# MCU.net
KiCad netlist of a schematic drawn in Altium Designer
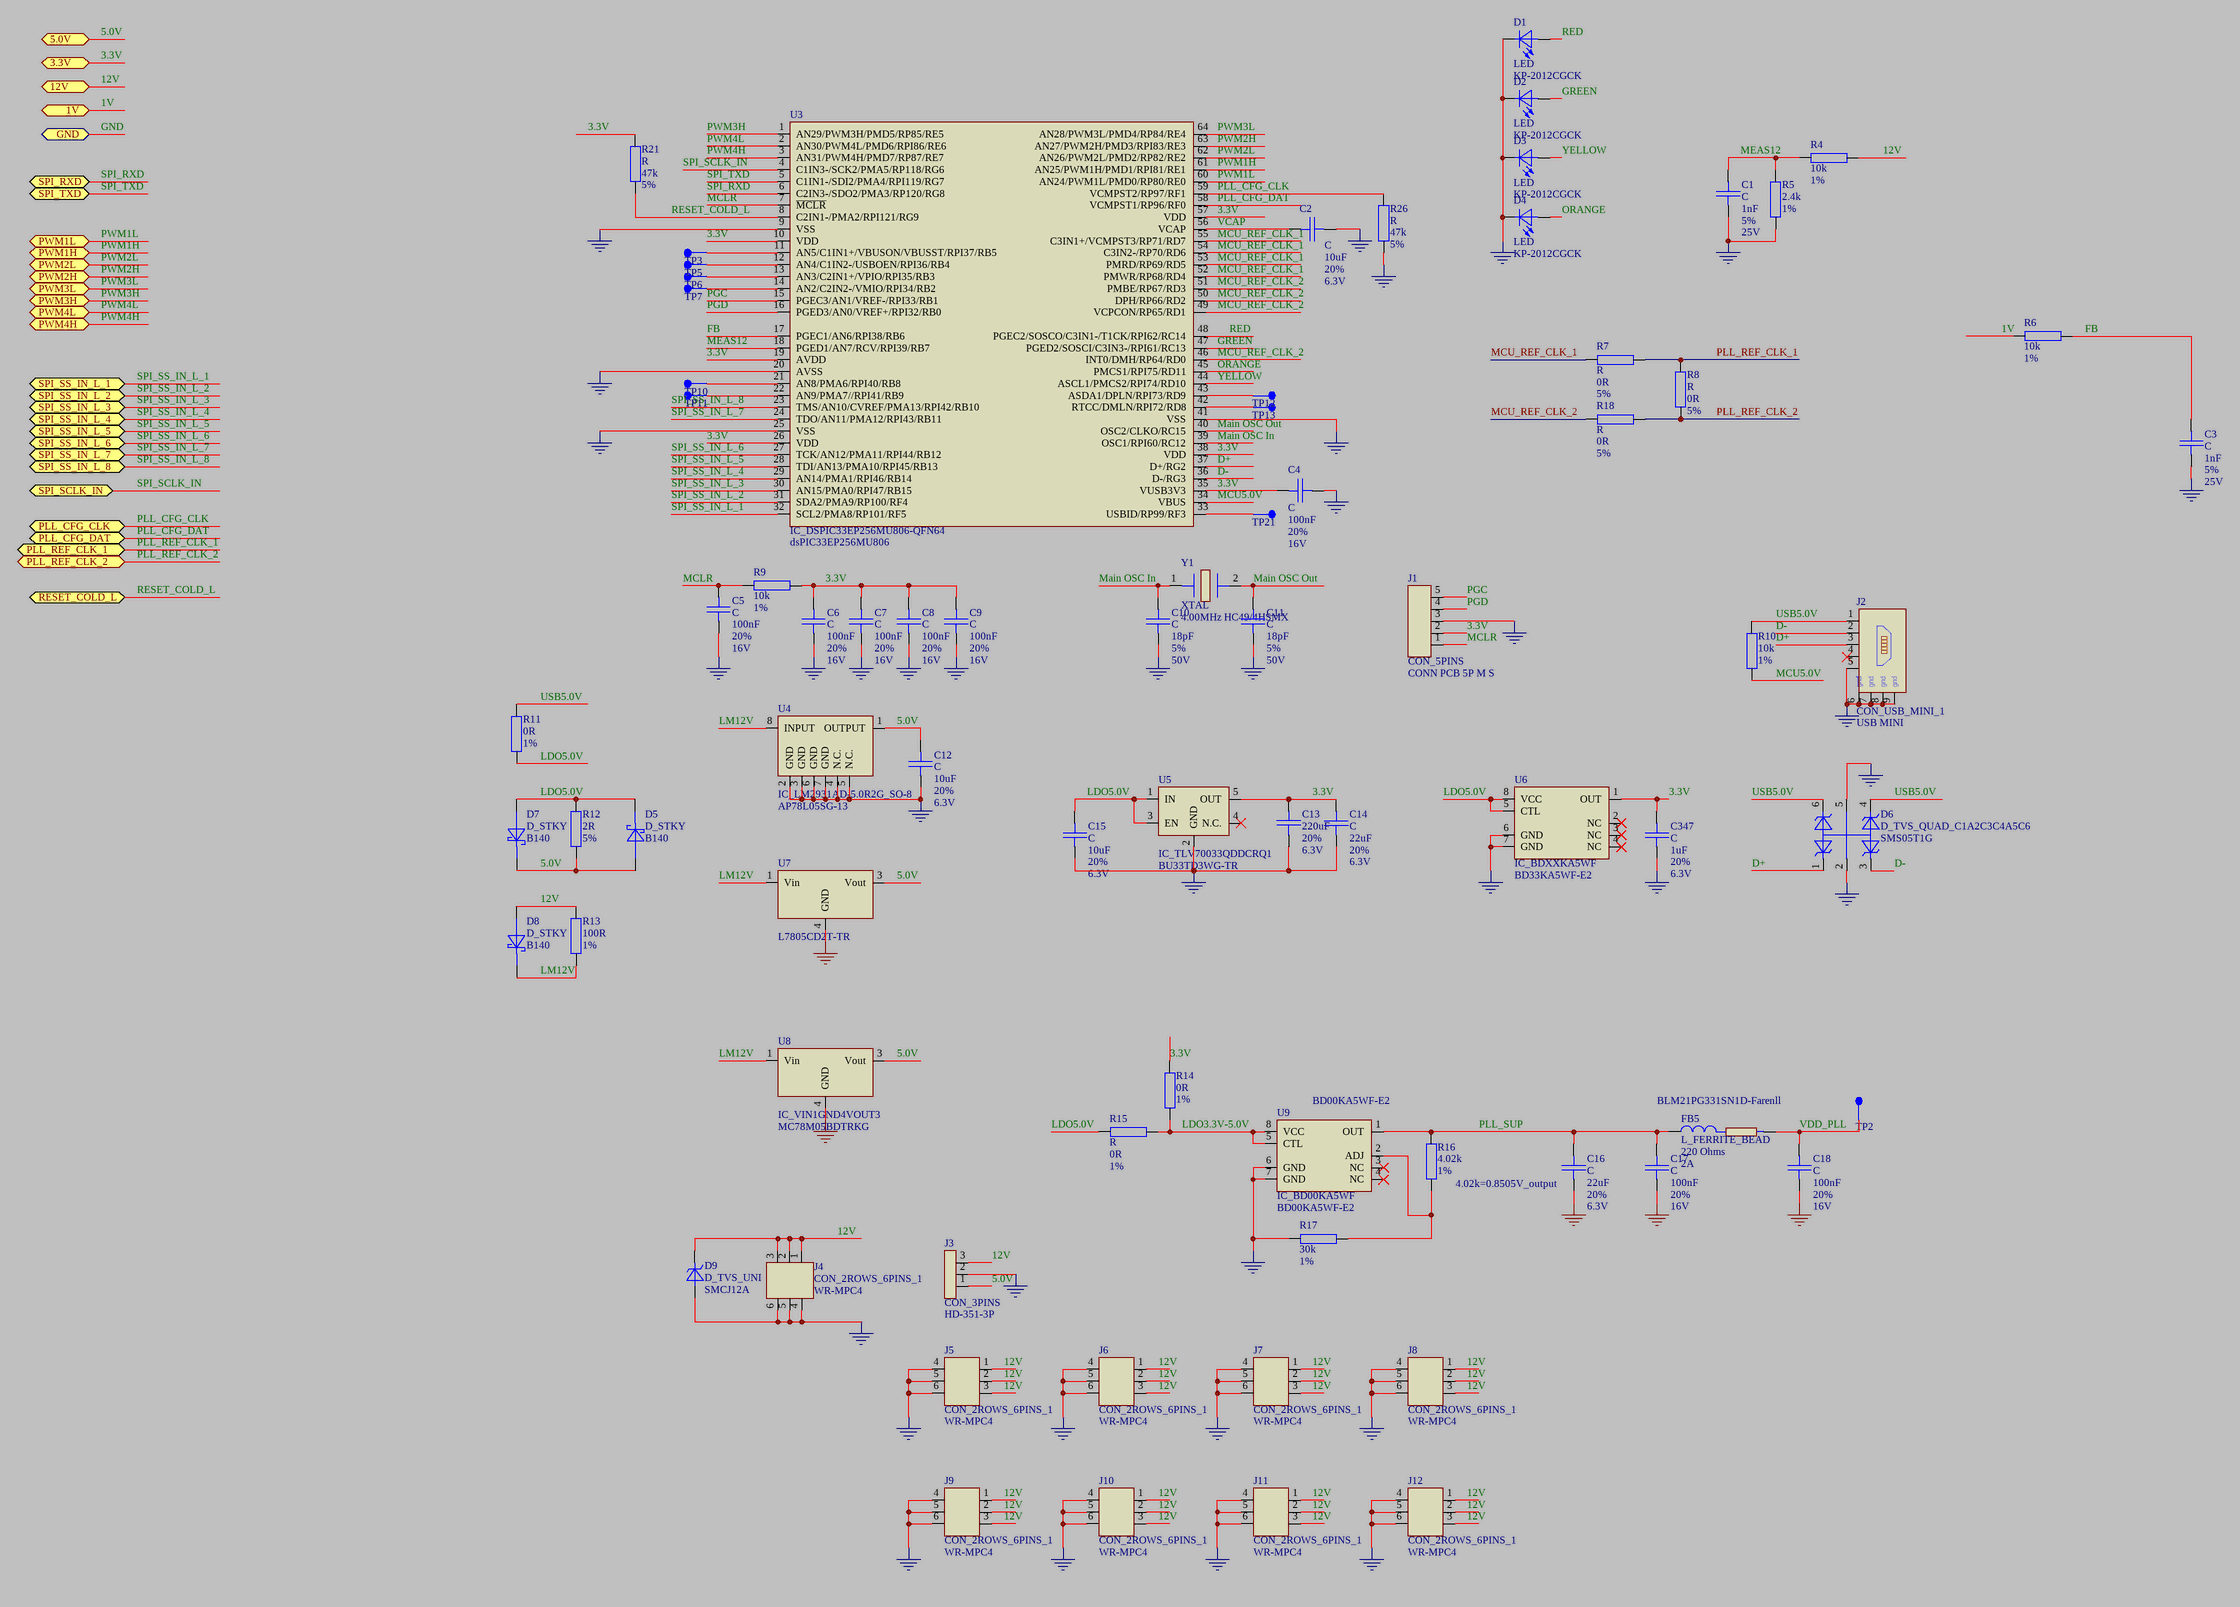
[diagram p0: MCU.SchDoc]

(export (version "E")
  (design (tool "Eeschema 10.0.6"))
  (components
    (comp (ref "C1")
      (value "C")
      (footprint "SMD_0603_CAPC1608X95N")
      (fields
        (field (name "DB_PART_NUMBER") "CAP000024113")
        (field (name "DB_VALUE") "1nF")
        (field (name "DB_TOLERANCE") "5%")
        (field (name "DB_VOLTAGE") "25V")
        (field (name "DB_MANUFACTURER_PART") "KEMET    C0603C102J3RAC")
      )
      (libsource (lib "Database_Libs1") (part "C"))
    )
    (comp (ref "C2")
      (value "C")
      (footprint "SMD_0603_CAPC1608X95N")
      (fields
        (field (name "DB_PART_NUMBER") "CAP000043646")
        (field (name "DB_VALUE") "10uF")
        (field (name "DB_TOLERANCE") "20%")
        (field (name "DB_VOLTAGE") "6.3V")
        (field (name "DB_MANUFACTURER_PART") "KEMET    C0603C106M9PAC")
      )
      (libsource (lib "Database_Libs1") (part "C"))
    )
    (comp (ref "C3")
      (value "C")
      (footprint "SMD_0603_CAPC1608X95N")
      (fields
        (field (name "DB_PART_NUMBER") "CAP000024113")
        (field (name "DB_VALUE") "1nF")
        (field (name "DB_TOLERANCE") "5%")
        (field (name "DB_VOLTAGE") "25V")
        (field (name "DB_MANUFACTURER_PART") "KEMET    C0603C102J3RAC")
      )
      (libsource (lib "Database_Libs1") (part "C"))
    )
    (comp (ref "C4")
      (value "C")
      (footprint "SMD_0402_CAPC1005X55N")
      (fields
        (field (name "DB_PART_NUMBER") "CAP000022751")
        (field (name "DB_VALUE") "100nF")
        (field (name "DB_TOLERANCE") "20%")
        (field (name "DB_VOLTAGE") "16V")
        (field (name "DB_MANUFACTURER_PART") "KEMET    C0402F104M4RAC")
      )
      (libsource (lib "Database_Libs1") (part "C"))
    )
    (comp (ref "C5")
      (value "C")
      (footprint "SMD_0402_CAPC1005X55N")
      (fields
        (field (name "DB_PART_NUMBER") "CAP000022751")
        (field (name "DB_VALUE") "100nF")
        (field (name "DB_TOLERANCE") "20%")
        (field (name "DB_VOLTAGE") "16V")
        (field (name "DB_MANUFACTURER_PART") "KEMET    C0402F104M4RAC")
      )
      (libsource (lib "Database_Libs1") (part "C"))
    )
    (comp (ref "C6")
      (value "C")
      (footprint "SMD_0402_CAPC1005X55N")
      (fields
        (field (name "DB_PART_NUMBER") "CAP000022751")
        (field (name "DB_VALUE") "100nF")
        (field (name "DB_TOLERANCE") "20%")
        (field (name "DB_VOLTAGE") "16V")
        (field (name "DB_MANUFACTURER_PART") "KEMET    C0402F104M4RAC")
      )
      (libsource (lib "Database_Libs1") (part "C"))
    )
    (comp (ref "C7")
      (value "C")
      (footprint "SMD_0402_CAPC1005X55N")
      (fields
        (field (name "DB_PART_NUMBER") "CAP000022751")
        (field (name "DB_VALUE") "100nF")
        (field (name "DB_TOLERANCE") "20%")
        (field (name "DB_VOLTAGE") "16V")
        (field (name "DB_MANUFACTURER_PART") "KEMET    C0402F104M4RAC")
      )
      (libsource (lib "Database_Libs1") (part "C"))
    )
    (comp (ref "C8")
      (value "C")
      (footprint "SMD_0402_CAPC1005X55N")
      (fields
        (field (name "DB_PART_NUMBER") "CAP000022751")
        (field (name "DB_VALUE") "100nF")
        (field (name "DB_TOLERANCE") "20%")
        (field (name "DB_VOLTAGE") "16V")
        (field (name "DB_MANUFACTURER_PART") "KEMET    C0402F104M4RAC")
      )
      (libsource (lib "Database_Libs1") (part "C"))
    )
    (comp (ref "C9")
      (value "C")
      (footprint "SMD_0402_CAPC1005X55N")
      (fields
        (field (name "DB_PART_NUMBER") "CAP000022751")
        (field (name "DB_VALUE") "100nF")
        (field (name "DB_TOLERANCE") "20%")
        (field (name "DB_VOLTAGE") "16V")
        (field (name "DB_MANUFACTURER_PART") "KEMET    C0402F104M4RAC")
      )
      (libsource (lib "Database_Libs1") (part "C"))
    )
    (comp (ref "C10")
      (value "C")
      (footprint "SMD_0603_CAPC1608X95N")
      (fields
        (field (name "DB_PART_NUMBER") "CAP000031922")
        (field (name "DB_VALUE") "18pF")
        (field (name "DB_TOLERANCE") "5%")
        (field (name "DB_VOLTAGE") "50V")
        (field (name "DB_MANUFACTURER_PART") "KEMET    C0603C180J5GAC")
      )
      (libsource (lib "Database_Libs1") (part "C"))
    )
    (comp (ref "C11")
      (value "C")
      (footprint "SMD_0603_CAPC1608X95N")
      (fields
        (field (name "DB_PART_NUMBER") "CAP000031922")
        (field (name "DB_VALUE") "18pF")
        (field (name "DB_TOLERANCE") "5%")
        (field (name "DB_VOLTAGE") "50V")
        (field (name "DB_MANUFACTURER_PART") "KEMET    C0603C180J5GAC")
      )
      (libsource (lib "Database_Libs1") (part "C"))
    )
    (comp (ref "C12")
      (value "C")
      (footprint "SMD_0603_CAPC1608X95N")
      (fields
        (field (name "DB_PART_NUMBER") "CAP000043646")
        (field (name "DB_VALUE") "10uF")
        (field (name "DB_TOLERANCE") "20%")
        (field (name "DB_VOLTAGE") "6.3V")
        (field (name "DB_MANUFACTURER_PART") "KEMET    C0603C106M9PAC")
      )
      (libsource (lib "Database_Libs1") (part "C"))
    )
    (comp (ref "C13")
      (value "C")
      (footprint "SMD_1210_CAPC3225X279N")
      (fields
        (field (name "DB_PART_NUMBER") "CAP000047355")
        (field (name "DB_VALUE") "220uF")
        (field (name "DB_TOLERANCE") "20%")
        (field (name "DB_VOLTAGE") "6.3V")
        (field (name "DB_MANUFACTURER_PART") "SAMSUNG    CL32A227MQVNNNE")
      )
      (libsource (lib "Database_Libs1") (part "C"))
    )
    (comp (ref "C14")
      (value "C")
      (footprint "SMD_0805_CAPC2012X145N")
      (fields
        (field (name "DB_PART_NUMBER") "CAP000043686")
        (field (name "DB_VALUE") "22uF")
        (field (name "DB_TOLERANCE") "20%")
        (field (name "DB_VOLTAGE") "6.3V")
        (field (name "DB_MANUFACTURER_PART") "KEMET    C0805C226M9PAC")
      )
      (libsource (lib "Database_Libs1") (part "C"))
    )
    (comp (ref "C15")
      (value "C")
      (footprint "SMD_0603_CAPC1608X95N")
      (fields
        (field (name "DB_PART_NUMBER") "CAP000043646")
        (field (name "DB_VALUE") "10uF")
        (field (name "DB_TOLERANCE") "20%")
        (field (name "DB_VOLTAGE") "6.3V")
        (field (name "DB_MANUFACTURER_PART") "KEMET    C0603C106M9PAC")
      )
      (libsource (lib "Database_Libs1") (part "C"))
    )
    (comp (ref "C16")
      (value "C")
      (footprint "SMD_0805_CAPC2012X145N")
      (fields
        (field (name "DB_PART_NUMBER") "CAP000043686")
        (field (name "DB_VALUE") "22uF")
        (field (name "DB_TOLERANCE") "20%")
        (field (name "DB_VOLTAGE") "6.3V")
        (field (name "DB_MANUFACTURER_PART") "KEMET    C0805C226M9PAC")
      )
      (libsource (lib "Database_Libs1") (part "C"))
    )
    (comp (ref "C17")
      (value "C")
      (footprint "SMD_0402_CAPC1005X55N")
      (fields
        (field (name "DB_PART_NUMBER") "CAP000022751")
        (field (name "DB_VALUE") "100nF")
        (field (name "DB_TOLERANCE") "20%")
        (field (name "DB_VOLTAGE") "16V")
        (field (name "DB_MANUFACTURER_PART") "KEMET    C0402F104M4RAC")
      )
      (libsource (lib "Database_Libs1") (part "C"))
    )
    (comp (ref "C18")
      (value "C")
      (footprint "SMD_0402_CAPC1005X55N")
      (fields
        (field (name "DB_PART_NUMBER") "CAP000022751")
        (field (name "DB_VALUE") "100nF")
        (field (name "DB_TOLERANCE") "20%")
        (field (name "DB_VOLTAGE") "16V")
        (field (name "DB_MANUFACTURER_PART") "KEMET    C0402F104M4RAC")
      )
      (libsource (lib "Database_Libs1") (part "C"))
    )
    (comp (ref "C347")
      (value "C")
      (footprint "SMD_0603_CAPC1608X95N")
      (fields
        (field (name "DB_PART_NUMBER") "CAP000043344")
        (field (name "DB_VALUE") "1uF")
        (field (name "DB_TOLERANCE") "20%")
        (field (name "DB_VOLTAGE") "6.3V")
        (field (name "DB_MANUFACTURER_PART") "KEMET    C0603C105M9PAC")
      )
      (libsource (lib "Database_Libs1") (part "C"))
    )
    (comp (ref "D1")
      (value "LED")
      (footprint "SMD_0805_LED2012X100N")
      (fields
        (field (name "DB_PART_NUMBER") "OPT000000096")
        (field (name "DB_VALUE") "KP-2012CGCK")
        (field (name "DB_MANUFACTURER_PART") "KINGBRIGHT       KP-2012CGCK")
      )
      (libsource (lib "Database_Libs1") (part "LED"))
    )
    (comp (ref "D2")
      (value "LED")
      (footprint "SMD_0805_LED2012X100N")
      (fields
        (field (name "DB_PART_NUMBER") "OPT000000096")
        (field (name "DB_VALUE") "KP-2012CGCK")
        (field (name "DB_MANUFACTURER_PART") "KINGBRIGHT       KP-2012CGCK")
      )
      (libsource (lib "Database_Libs1") (part "LED"))
    )
    (comp (ref "D3")
      (value "LED")
      (footprint "SMD_0805_LED2012X100N")
      (fields
        (field (name "DB_PART_NUMBER") "OPT000000096")
        (field (name "DB_VALUE") "KP-2012CGCK")
        (field (name "DB_MANUFACTURER_PART") "KINGBRIGHT       KP-2012CGCK")
      )
      (libsource (lib "Database_Libs1") (part "LED"))
    )
    (comp (ref "D4")
      (value "LED")
      (footprint "SMD_0805_LED2012X100N")
      (fields
        (field (name "DB_PART_NUMBER") "OPT000000096")
        (field (name "DB_VALUE") "KP-2012CGCK")
        (field (name "DB_MANUFACTURER_PART") "KINGBRIGHT       KP-2012CGCK")
      )
      (libsource (lib "Database_Libs1") (part "LED"))
    )
    (comp (ref "D5")
      (value "D_STKY")
      (footprint "SMD_DO214AC_SMA")
      (fields
        (field (name "DB_PART_NUMBER") "DDE000000580")
        (field (name "DB_VALUE") "B140")
        (field (name "DB_MANUFACTURER_PART") "Diodes        B140")
      )
      (libsource (lib "Database_Libs1") (part "D_STKY"))
    )
    (comp (ref "D6")
      (value "D_TVS_QUAD_C1A2C3C4A5C6")
      (footprint "SMD_SOT457_SOT95P275X110-6N")
      (fields
        (field (name "DB_PART_NUMBER") "DDE000002846")
        (field (name "DB_VALUE") "SMS05T1G")
        (field (name "DB_MANUFACTURER_PART") "ON SEMICONDUCTOR        SMS05T1G")
      )
      (libsource (lib "Database_Libs1") (part "D_TVS_QUAD_C1A2C3C4A5C6"))
    )
    (comp (ref "D7")
      (value "D_STKY")
      (footprint "SMD_DO214AC_SMA")
      (fields
        (field (name "DB_PART_NUMBER") "DDE000000580")
        (field (name "DB_VALUE") "B140")
        (field (name "DB_MANUFACTURER_PART") "Diodes        B140")
      )
      (libsource (lib "Database_Libs1") (part "D_STKY"))
    )
    (comp (ref "D8")
      (value "D_STKY")
      (footprint "SMD_DO214AC_SMA")
      (fields
        (field (name "DB_PART_NUMBER") "DDE000000580")
        (field (name "DB_VALUE") "B140")
        (field (name "DB_MANUFACTURER_PART") "Diodes        B140")
      )
      (libsource (lib "Database_Libs1") (part "D_STKY"))
    )
    (comp (ref "D9")
      (value "D_TVS_UNI")
      (footprint "SMD_DO214AC_SMC")
      (fields
        (field (name "DB_PART_NUMBER") "DDE000001725")
        (field (name "DB_VALUE") "SMCJ12A")
        (field (name "DB_MANUFACTURER_PART") "Diodes        SMCJ12A")
      )
      (libsource (lib "Database_Libs1") (part "D_TVS_UNI"))
    )
    (comp (ref "FB5")
      (value "L_FERRITE_BEAD")
      (footprint "SMD_0805_INDC2012X105N")
      (fields
        (field (name "DB_PART_NUMBER") "IND000000029")
        (field (name "DB_VALUE") "220 Ohms")
        (field (name "DB_CURRENT") "2A")
        (field (name "DB_MANUFACTURER_PART") "MURATA       BLM21PG221SN1D")
      )
      (libsource (lib "Database_Libs1") (part "L_FERRITE_BEAD"))
    )
    (comp (ref "J1")
      (value "CON_5PINS")
      (footprint "PTH_HDRV05W64P254_1X05")
      (fields
        (field (name "DB_PART_NUMBER") "CON000000006")
        (field (name "DB_VALUE") "CONN PCB 5P M S")
        (field (name "DB_MANUFACTURER_PART") "W+P        143-12-005-00")
      )
      (libsource (lib "Database_Libs1") (part "CON_5PINS"))
    )
    (comp (ref "J2")
      (value "CON_USB_MINI_1")
      (footprint "SMD_CON-CVILUX-CU04-SCM15B0")
      (fields
        (field (name "DB_PART_NUMBER") "CON000000048")
        (field (name "DB_VALUE") "USB MINI")
        (field (name "DB_MANUFACTURER_PART") "CVILUX       CU04-SCM15B0-R0-LF")
      )
      (libsource (lib "Database_Libs1") (part "CON_USB_MINI_1"))
    )
    (comp (ref "J3")
      (value "CON_3PINS")
      (footprint "PTH_CON_HD-351-3P")
      (fields
        (field (name "DB_PART_NUMBER") "CON000000272")
        (field (name "DB_VALUE") "HD-351-3P")
        (field (name "DB_MANUFACTURER_PART") "HOW DER      HD-351-3P")
      )
      (libsource (lib "Database_Libs1") (part "CON_3PINS"))
    )
    (comp (ref "J4")
      (value "CON_2ROWS_6PINS_1")
      (footprint "PTH_CON_WR-MRC4-6P_S")
      (fields
        (field (name "DB_PART_NUMBER") "CON000000279")
        (field (name "DB_VALUE") "WR-MPC4")
        (field (name "DB_MANUFACTURER_PART") "WE        	649 006 211 22")
      )
      (libsource (lib "Database_Libs1") (part "CON_2ROWS_6PINS_1"))
    )
    (comp (ref "J5")
      (value "CON_2ROWS_6PINS_1")
      (footprint "PTH_CON_WR-MRC4-6P_S")
      (fields
        (field (name "DB_PART_NUMBER") "CON000000279")
        (field (name "DB_VALUE") "WR-MPC4")
        (field (name "DB_MANUFACTURER_PART") "WE        	649 006 211 22")
      )
      (libsource (lib "Database_Libs1") (part "CON_2ROWS_6PINS_1"))
    )
    (comp (ref "J6")
      (value "CON_2ROWS_6PINS_1")
      (footprint "PTH_CON_WR-MRC4-6P_S")
      (fields
        (field (name "DB_PART_NUMBER") "CON000000279")
        (field (name "DB_VALUE") "WR-MPC4")
        (field (name "DB_MANUFACTURER_PART") "WE        	649 006 211 22")
      )
      (libsource (lib "Database_Libs1") (part "CON_2ROWS_6PINS_1"))
    )
    (comp (ref "J7")
      (value "CON_2ROWS_6PINS_1")
      (footprint "PTH_CON_WR-MRC4-6P_S")
      (fields
        (field (name "DB_PART_NUMBER") "CON000000279")
        (field (name "DB_VALUE") "WR-MPC4")
        (field (name "DB_MANUFACTURER_PART") "WE        	649 006 211 22")
      )
      (libsource (lib "Database_Libs1") (part "CON_2ROWS_6PINS_1"))
    )
    (comp (ref "J8")
      (value "CON_2ROWS_6PINS_1")
      (footprint "PTH_CON_WR-MRC4-6P_S")
      (fields
        (field (name "DB_PART_NUMBER") "CON000000279")
        (field (name "DB_VALUE") "WR-MPC4")
        (field (name "DB_MANUFACTURER_PART") "WE        	649 006 211 22")
      )
      (libsource (lib "Database_Libs1") (part "CON_2ROWS_6PINS_1"))
    )
    (comp (ref "J9")
      (value "CON_2ROWS_6PINS_1")
      (footprint "PTH_CON_WR-MRC4-6P_S")
      (fields
        (field (name "DB_PART_NUMBER") "CON000000279")
        (field (name "DB_VALUE") "WR-MPC4")
        (field (name "DB_MANUFACTURER_PART") "WE        	649 006 211 22")
      )
      (libsource (lib "Database_Libs1") (part "CON_2ROWS_6PINS_1"))
    )
    (comp (ref "J10")
      (value "CON_2ROWS_6PINS_1")
      (footprint "PTH_CON_WR-MRC4-6P_S")
      (fields
        (field (name "DB_PART_NUMBER") "CON000000279")
        (field (name "DB_VALUE") "WR-MPC4")
        (field (name "DB_MANUFACTURER_PART") "WE        	649 006 211 22")
      )
      (libsource (lib "Database_Libs1") (part "CON_2ROWS_6PINS_1"))
    )
    (comp (ref "J11")
      (value "CON_2ROWS_6PINS_1")
      (footprint "PTH_CON_WR-MRC4-6P_S")
      (fields
        (field (name "DB_PART_NUMBER") "CON000000279")
        (field (name "DB_VALUE") "WR-MPC4")
        (field (name "DB_MANUFACTURER_PART") "WE        	649 006 211 22")
      )
      (libsource (lib "Database_Libs1") (part "CON_2ROWS_6PINS_1"))
    )
    (comp (ref "J12")
      (value "CON_2ROWS_6PINS_1")
      (footprint "PTH_CON_WR-MRC4-6P_S")
      (fields
        (field (name "DB_PART_NUMBER") "CON000000279")
        (field (name "DB_VALUE") "WR-MPC4")
        (field (name "DB_MANUFACTURER_PART") "WE        	649 006 211 22")
      )
      (libsource (lib "Database_Libs1") (part "CON_2ROWS_6PINS_1"))
    )
    (comp (ref "R4")
      (value "R")
      (footprint "SMD_0603_RESC1608X55N")
      (fields
        (field (name "DB_PART_NUMBER") "RES000008663")
        (field (name "DB_VALUE") "10k")
        (field (name "DB_TOLERANCE") "1%")
        (field (name "DB_MANUFACTURER_PART") "YAGEO    RC0603FR-0710KL")
      )
      (libsource (lib "Database_Libs1") (part "R"))
    )
    (comp (ref "R5")
      (value "R")
      (footprint "SMD_0603_RESC1608X55N")
      (fields
        (field (name "DB_PART_NUMBER") "RES000006261")
        (field (name "DB_VALUE") "2.4k")
        (field (name "DB_TOLERANCE") "1%")
        (field (name "DB_MANUFACTURER_PART") "YAGEO    RC0603FR-072K4")
      )
      (libsource (lib "Database_Libs1") (part "R"))
    )
    (comp (ref "R6")
      (value "R")
      (footprint "SMD_0603_RESC1608X55N")
      (fields
        (field (name "DB_PART_NUMBER") "RES000008663")
        (field (name "DB_VALUE") "10k")
        (field (name "DB_TOLERANCE") "1%")
        (field (name "DB_MANUFACTURER_PART") "YAGEO    RC0603FR-0710KL")
      )
      (libsource (lib "Database_Libs1") (part "R"))
    )
    (comp (ref "R7")
      (value "R")
      (footprint "SMD_0603_RESC1608X55N")
      (fields
        (field (name "DB_PART_NUMBER") "RES000006349")
        (field (name "DB_VALUE") "0R")
        (field (name "DB_TOLERANCE") "5%")
        (field (name "DB_MANUFACTURER_PART") "YAGEO    RC0603JR-070R")
      )
      (libsource (lib "Database_Libs1") (part "R"))
    )
    (comp (ref "R8")
      (value "R")
      (footprint "SMD_0603_RESC1608X55N")
      (fields
        (field (name "DB_PART_NUMBER") "RES000006349")
        (field (name "DB_VALUE") "0R")
        (field (name "DB_TOLERANCE") "5%")
        (field (name "DB_MANUFACTURER_PART") "YAGEO    RC0603JR-070R")
      )
      (libsource (lib "Database_Libs1") (part "R"))
    )
    (comp (ref "R9")
      (value "R")
      (footprint "SMD_0603_RESC1608X55N")
      (fields
        (field (name "DB_PART_NUMBER") "RES000008663")
        (field (name "DB_VALUE") "10k")
        (field (name "DB_TOLERANCE") "1%")
        (field (name "DB_MANUFACTURER_PART") "YAGEO    RC0603FR-0710KL")
      )
      (libsource (lib "Database_Libs1") (part "R"))
    )
    (comp (ref "R10")
      (value "R")
      (footprint "SMD_0603_RESC1608X55N")
      (fields
        (field (name "DB_PART_NUMBER") "RES000008663")
        (field (name "DB_VALUE") "10k")
        (field (name "DB_TOLERANCE") "1%")
        (field (name "DB_MANUFACTURER_PART") "YAGEO    RC0603FR-0710KL")
      )
      (libsource (lib "Database_Libs1") (part "R"))
    )
    (comp (ref "R11")
      (value "R")
      (footprint "SMD_0603_RESC1608X55N")
      (fields
        (field (name "DB_PART_NUMBER") "RES000008926")
        (field (name "DB_VALUE") "0R")
        (field (name "DB_TOLERANCE") "1%")
        (field (name "DB_MANUFACTURER_PART") "YAGEO    AC0603FR-070RL")
      )
      (libsource (lib "Database_Libs1") (part "R"))
    )
    (comp (ref "R12")
      (value "R")
      (footprint "SMD_1206_RESC3216X65N")
      (fields
        (field (name "DB_PART_NUMBER") "RES000007051")
        (field (name "DB_VALUE") "2R")
        (field (name "DB_TOLERANCE") "5%")
        (field (name "DB_MANUFACTURER_PART") "YAGEO    RC1206JR-072R")
      )
      (libsource (lib "Database_Libs1") (part "R"))
    )
    (comp (ref "R13")
      (value "R")
      (footprint "SMD_1206_RESC3216X65N")
      (fields
        (field (name "DB_PART_NUMBER") "RES000006922")
        (field (name "DB_VALUE") "100R")
        (field (name "DB_TOLERANCE") "1%")
        (field (name "DB_MANUFACTURER_PART") "YAGEO    RC1206FR-07100R")
      )
      (libsource (lib "Database_Libs1") (part "R"))
    )
    (comp (ref "R14")
      (value "R")
      (footprint "SMD_1206_RESC3216X65N")
      (fields
        (field (name "DB_PART_NUMBER") "RES000008756")
        (field (name "DB_VALUE") "0R")
        (field (name "DB_TOLERANCE") "1%")
        (field (name "DB_MANUFACTURER_PART") "YAGEO    AC1206FR-070RL")
      )
      (libsource (lib "Database_Libs1") (part "R"))
    )
    (comp (ref "R15")
      (value "R")
      (footprint "SMD_1206_RESC3216X65N")
      (fields
        (field (name "DB_PART_NUMBER") "RES000008756")
        (field (name "DB_VALUE") "0R")
        (field (name "DB_TOLERANCE") "1%")
        (field (name "DB_MANUFACTURER_PART") "YAGEO    AC1206FR-070RL")
      )
      (libsource (lib "Database_Libs1") (part "R"))
    )
    (comp (ref "R16")
      (value "R")
      (footprint "SMD_0603_RESC1608X55N")
      (fields
        (field (name "DB_PART_NUMBER") "RES000001499")
        (field (name "DB_VALUE") "4.02k")
        (field (name "DB_TOLERANCE") "1%")
        (field (name "DB_MANUFACTURER_PART") "YAGEO    RC0603FR-074K02")
      )
      (libsource (lib "Database_Libs1") (part "R"))
    )
    (comp (ref "R17")
      (value "R")
      (footprint "SMD_0603_RESC1608X55N")
      (fields
        (field (name "DB_PART_NUMBER") "RES000006287")
        (field (name "DB_VALUE") "30k")
        (field (name "DB_TOLERANCE") "1%")
        (field (name "DB_MANUFACTURER_PART") "YAGEO    RC0603FR-0730K")
      )
      (libsource (lib "Database_Libs1") (part "R"))
    )
    (comp (ref "R18")
      (value "R")
      (footprint "SMD_0603_RESC1608X55N")
      (fields
        (field (name "DB_PART_NUMBER") "RES000006349")
        (field (name "DB_VALUE") "0R")
        (field (name "DB_TOLERANCE") "5%")
        (field (name "DB_MANUFACTURER_PART") "YAGEO    RC0603JR-070R")
      )
      (libsource (lib "Database_Libs1") (part "R"))
    )
    (comp (ref "R21")
      (value "R")
      (footprint "SMD_0603_RESC1608X55N")
      (fields
        (field (name "DB_PART_NUMBER") "RES000006462")
        (field (name "DB_VALUE") "47k")
        (field (name "DB_TOLERANCE") "5%")
        (field (name "DB_MANUFACTURER_PART") "YAGEO    RC0603JR-0747K")
      )
      (libsource (lib "Database_Libs1") (part "R"))
    )
    (comp (ref "R26")
      (value "R")
      (footprint "SMD_0603_RESC1608X55N")
      (fields
        (field (name "DB_PART_NUMBER") "RES000006462")
        (field (name "DB_VALUE") "47k")
        (field (name "DB_TOLERANCE") "5%")
        (field (name "DB_MANUFACTURER_PART") "YAGEO    RC0603JR-0747K")
      )
      (libsource (lib "Database_Libs1") (part "R"))
    )
    (comp (ref "TP2")
      (value "TEST_POINT_1")
      (footprint "SMD_TP_100-254")
      (fields (field (name "DB_PART_NUMBER") "TPO000000001"))
      (libsource (lib "Database_Libs1") (part "TEST_POINT_1"))
    )
    (comp (ref "TP3")
      (value "TEST_POINT_1")
      (footprint "SMD_TP_100-254")
      (fields (field (name "DB_PART_NUMBER") "TPO000000001"))
      (libsource (lib "Database_Libs1") (part "TEST_POINT_1"))
    )
    (comp (ref "TP5")
      (value "TEST_POINT_1")
      (footprint "SMD_TP_100-254")
      (fields (field (name "DB_PART_NUMBER") "TPO000000001"))
      (libsource (lib "Database_Libs1") (part "TEST_POINT_1"))
    )
    (comp (ref "TP6")
      (value "TEST_POINT_1")
      (footprint "SMD_TP_100-254")
      (fields (field (name "DB_PART_NUMBER") "TPO000000001"))
      (libsource (lib "Database_Libs1") (part "TEST_POINT_1"))
    )
    (comp (ref "TP7")
      (value "TEST_POINT_1")
      (footprint "SMD_TP_100-254")
      (fields (field (name "DB_PART_NUMBER") "TPO000000001"))
      (libsource (lib "Database_Libs1") (part "TEST_POINT_1"))
    )
    (comp (ref "TP10")
      (value "TEST_POINT_1")
      (footprint "SMD_TP_100-254")
      (fields (field (name "DB_PART_NUMBER") "TPO000000001"))
      (libsource (lib "Database_Libs1") (part "TEST_POINT_1"))
    )
    (comp (ref "TP11")
      (value "TEST_POINT_1")
      (footprint "SMD_TP_100-254")
      (fields (field (name "DB_PART_NUMBER") "TPO000000001"))
      (libsource (lib "Database_Libs1") (part "TEST_POINT_1"))
    )
    (comp (ref "TP12")
      (value "TEST_POINT_1")
      (footprint "SMD_TP_100-254")
      (fields (field (name "DB_PART_NUMBER") "TPO000000001"))
      (libsource (lib "Database_Libs1") (part "TEST_POINT_1"))
    )
    (comp (ref "TP13")
      (value "TEST_POINT_1")
      (footprint "SMD_TP_100-254")
      (fields (field (name "DB_PART_NUMBER") "TPO000000001"))
      (libsource (lib "Database_Libs1") (part "TEST_POINT_1"))
    )
    (comp (ref "TP21")
      (value "TEST_POINT_1")
      (footprint "SMD_TP_100-254")
      (fields (field (name "DB_PART_NUMBER") "TPO000000001"))
      (libsource (lib "Database_Libs1") (part "TEST_POINT_1"))
    )
    (comp (ref "U3")
      (value "IC_DSPIC33EP256MU806-QFN64")
      (footprint "SMD_QFP50P1200X1200X120-64N")
      (fields
        (field (name "DB_PART_NUMBER") "MCU000000070")
        (field (name "DB_VALUE") "dsPIC33EP256MU806")
        (field (name "DB_MANUFACTURER_PART") "MICROCHIP        DSPIC33EP256MU806-E/PT")
      )
      (libsource (lib "Database_Libs1") (part "IC_DSPIC33EP256MU806-QFN64"))
    )
    (comp (ref "U4")
      (value "IC_LM2931AD-5.0R2G_SO-8")
      (footprint "SMD_SOIC127P600X175-8N")
      (fields
        (field (name "DB_PART_NUMBER") "PSU000000125")
        (field (name "DB_VALUE") "AP78L05SG-13")
        (field (name "DB_MANUFACTURER_PART") "DIODES        AP78L05SG-13")
      )
      (libsource (lib "Database_Libs1") (part "IC_LM2931AD-5.0R2G_SO-8"))
    )
    (comp (ref "U5")
      (value "IC_TLV70033QDDCRQ1")
      (footprint "SMD_SOT95P280X135-5N")
      (fields
        (field (name "DB_PART_NUMBER") "PSU000000126")
        (field (name "DB_VALUE") "BU33TD3WG-TR")
        (field (name "DB_MANUFACTURER_PART") "ROHM     BU33TD3WG-TR")
      )
      (libsource (lib "Database_Libs1") (part "IC_TLV70033QDDCRQ1"))
    )
    (comp (ref "U6")
      (value "IC_BDXXKA5WF")
      (footprint "SMD_SOIC127P620X160-8N")
      (fields
        (field (name "DB_PART_NUMBER") "PSU000000127")
        (field (name "DB_VALUE") "BD33KA5WF-E2")
        (field (name "DB_MANUFACTURER_PART") "ROHM        BD33KA5WF-E2")
      )
      (libsource (lib "Database_Libs1") (part "IC_BDXXKA5WF"))
    )
    (comp (ref "U7")
      (value "IC_IN1OUT3GND4")
      (footprint "SMD_TO254P1542X460-3_4N")
      (fields
        (field (name "DB_PART_NUMBER") "PSU000000129")
        (field (name "DB_VALUE") "L7805CD2T-TR")
        (field (name "DB_MANUFACTURER_PART") "ST       L7805CD2T-TR")
      )
      (libsource (lib "Database_Libs1") (part "IC_IN1OUT3GND4"))
    )
    (comp (ref "U8")
      (value "IC_VIN1GND4VOUT3")
      (footprint "SMD_TO229P991X239-4N_DPAK")
      (fields
        (field (name "DB_PART_NUMBER") "PSU000000031")
        (field (name "DB_VALUE") "MC78M05BDTRKG")
        (field (name "DB_MANUFACTURER_PART") "ON Semiconductor       MC78M05BDTRKG")
      )
      (libsource (lib "Database_Libs1") (part "IC_VIN1GND4VOUT3"))
    )
    (comp (ref "U9")
      (value "IC_BD00KA5WF")
      (footprint "SMD_SOIC127P620X160-8N")
      (fields
        (field (name "DB_PART_NUMBER") "PSU000000128")
        (field (name "DB_VALUE") "BD00KA5WF-E2")
        (field (name "DB_MANUFACTURER_PART") "ROHM        BD00KA5WF-E2")
      )
      (libsource (lib "Database_Libs1") (part "IC_BD00KA5WF"))
    )
    (comp (ref "Y1")
      (value "XTAL")
      (footprint "SMD_HC49_XTAL1140X480X420N")
      (fields
        (field (name "DB_PART_NUMBER") "OSC000000012")
        (field (name "DB_VALUE") "4.00MHz HC49/4HSMX")
        (field (name "DB_MANUFACTURER_PART") "IQD       4.00MHz HC49/4HSMX")
      )
      (libsource (lib "Database_Libs1") (part "XTAL"))
    )
  )
  (nets
    (net (code "1") (name "/1V") (class "Default")
      (node (ref "R6") (pin "2") (pinfunction "2_2") (pintype "passive"))
    )
    (net (code "2") (name "/3.3V") (class "Default")
      (node (ref "C13") (pin "2") (pinfunction "2_2") (pintype "passive"))
      (node (ref "C14") (pin "1") (pinfunction "1_1") (pintype "passive"))
      (node (ref "C347") (pin "1") (pinfunction "1_1") (pintype "passive"))
      (node (ref "C4") (pin "1") (pinfunction "1_1") (pintype "passive"))
      (node (ref "C6") (pin "1") (pinfunction "1_1") (pintype "passive"))
      (node (ref "C7") (pin "1") (pinfunction "1_1") (pintype "passive"))
      (node (ref "C8") (pin "1") (pinfunction "1_1") (pintype "passive"))
      (node (ref "C9") (pin "1") (pinfunction "1_1") (pintype "passive"))
      (node (ref "J1") (pin "2") (pinfunction "2_2") (pintype "passive"))
      (node (ref "R14") (pin "2") (pinfunction "2_2") (pintype "passive"))
      (node (ref "R21") (pin "1") (pinfunction "1_1") (pintype "passive"))
      (node (ref "R9") (pin "2") (pinfunction "2_2") (pintype "passive"))
      (node (ref "U3") (pin "10") (pinfunction "VDD_10") (pintype "passive"))
      (node (ref "U3") (pin "19") (pinfunction "AVDD_19") (pintype "passive"))
      (node (ref "U3") (pin "26") (pinfunction "VDD_26") (pintype "passive"))
      (node (ref "U3") (pin "35") (pinfunction "VUSB3V3_35") (pintype "passive"))
      (node (ref "U3") (pin "38") (pinfunction "VDD_38") (pintype "passive"))
      (node (ref "U3") (pin "57") (pinfunction "VDD_57") (pintype "passive"))
      (node (ref "U5") (pin "5") (pinfunction "OUT_5") (pintype "passive"))
      (node (ref "U6") (pin "1") (pinfunction "OUT_1") (pintype "passive"))
    )
    (net (code "3") (name "/5.0V") (class "Default")
      (node (ref "C12") (pin "1") (pinfunction "1_1") (pintype "passive"))
      (node (ref "D5") (pin "2") (pinfunction "A_2") (pintype "passive"))
      (node (ref "D7") (pin "1") (pinfunction "C_1") (pintype "passive"))
      (node (ref "J3") (pin "1") (pinfunction "1_1") (pintype "passive"))
      (node (ref "R12") (pin "1") (pinfunction "1_1") (pintype "passive"))
      (node (ref "U4") (pin "1") (pinfunction "OUTPUT_1") (pintype "passive"))
      (node (ref "U7") (pin "3") (pinfunction "Vout_3") (pintype "passive"))
      (node (ref "U8") (pin "3") (pinfunction "Vout_3") (pintype "passive"))
    )
    (net (code "4") (name "/12V") (class "Default")
      (node (ref "D8") (pin "2") (pinfunction "A_2") (pintype "passive"))
      (node (ref "D9") (pin "1") (pinfunction "C_1") (pintype "passive"))
      (node (ref "J10") (pin "1") (pinfunction "1_1") (pintype "passive"))
      (node (ref "J10") (pin "2") (pinfunction "2_2") (pintype "passive"))
      (node (ref "J10") (pin "3") (pinfunction "3_3") (pintype "passive"))
      (node (ref "J11") (pin "1") (pinfunction "1_1") (pintype "passive"))
      (node (ref "J11") (pin "2") (pinfunction "2_2") (pintype "passive"))
      (node (ref "J11") (pin "3") (pinfunction "3_3") (pintype "passive"))
      (node (ref "J12") (pin "1") (pinfunction "1_1") (pintype "passive"))
      (node (ref "J12") (pin "2") (pinfunction "2_2") (pintype "passive"))
      (node (ref "J12") (pin "3") (pinfunction "3_3") (pintype "passive"))
      (node (ref "J3") (pin "3") (pinfunction "3_3") (pintype "passive"))
      (node (ref "J4") (pin "1") (pinfunction "1_1") (pintype "passive"))
      (node (ref "J4") (pin "2") (pinfunction "2_2") (pintype "passive"))
      (node (ref "J4") (pin "3") (pinfunction "3_3") (pintype "passive"))
      (node (ref "J5") (pin "1") (pinfunction "1_1") (pintype "passive"))
      (node (ref "J5") (pin "2") (pinfunction "2_2") (pintype "passive"))
      (node (ref "J5") (pin "3") (pinfunction "3_3") (pintype "passive"))
      (node (ref "J6") (pin "1") (pinfunction "1_1") (pintype "passive"))
      (node (ref "J6") (pin "2") (pinfunction "2_2") (pintype "passive"))
      (node (ref "J6") (pin "3") (pinfunction "3_3") (pintype "passive"))
      (node (ref "J7") (pin "1") (pinfunction "1_1") (pintype "passive"))
      (node (ref "J7") (pin "2") (pinfunction "2_2") (pintype "passive"))
      (node (ref "J7") (pin "3") (pinfunction "3_3") (pintype "passive"))
      (node (ref "J8") (pin "1") (pinfunction "1_1") (pintype "passive"))
      (node (ref "J8") (pin "2") (pinfunction "2_2") (pintype "passive"))
      (node (ref "J8") (pin "3") (pinfunction "3_3") (pintype "passive"))
      (node (ref "J9") (pin "1") (pinfunction "1_1") (pintype "passive"))
      (node (ref "J9") (pin "2") (pinfunction "2_2") (pintype "passive"))
      (node (ref "J9") (pin "3") (pinfunction "3_3") (pintype "passive"))
      (node (ref "R13") (pin "2") (pinfunction "2_2") (pintype "passive"))
      (node (ref "R4") (pin "1") (pinfunction "1_1") (pintype "passive"))
    )
    (net (code "5") (name "/D+") (class "Default")
      (node (ref "D6") (pin "1") (pinfunction "1_1") (pintype "passive"))
      (node (ref "J2") (pin "3") (pinfunction "3_3") (pintype "passive"))
      (node (ref "U3") (pin "37") (pinfunction "D+/RG2_37") (pintype "passive"))
    )
    (net (code "6") (name "/D-") (class "Default")
      (node (ref "D6") (pin "3") (pinfunction "3_3") (pintype "passive"))
      (node (ref "J2") (pin "2") (pinfunction "2_2") (pintype "passive"))
      (node (ref "U3") (pin "36") (pinfunction "D-/RG3_36") (pintype "passive"))
    )
    (net (code "7") (name "/FB") (class "Default")
      (node (ref "C3") (pin "1") (pinfunction "1_1") (pintype "passive"))
      (node (ref "R6") (pin "1") (pinfunction "1_1") (pintype "passive"))
      (node (ref "U3") (pin "17") (pinfunction "PGEC1/AN6/RPI38/RB6_17") (pintype "passive"))
    )
    (net (code "8") (name "/GREEN") (class "Default")
      (node (ref "D2") (pin "2") (pinfunction "A_2") (pintype "passive"))
      (node (ref "U3") (pin "47") (pinfunction "PGED2/SOSCI/C3IN3-/RPI61/RC13_47") (pintype "passive"))
    )
    (net (code "9") (name "/LDO3.3V-5.0V") (class "Default")
      (node (ref "R14") (pin "1") (pinfunction "1_1") (pintype "passive"))
      (node (ref "R15") (pin "1") (pinfunction "1_1") (pintype "passive"))
      (node (ref "U9") (pin "5") (pinfunction "CTL_5") (pintype "passive"))
      (node (ref "U9") (pin "8") (pinfunction "VCC_8") (pintype "passive"))
    )
    (net (code "10") (name "/LDO5.0V") (class "Default")
      (node (ref "C15") (pin "1") (pinfunction "1_1") (pintype "passive"))
      (node (ref "D5") (pin "1") (pinfunction "C_1") (pintype "passive"))
      (node (ref "D7") (pin "2") (pinfunction "A_2") (pintype "passive"))
      (node (ref "R11") (pin "1") (pinfunction "1_1") (pintype "passive"))
      (node (ref "R12") (pin "2") (pinfunction "2_2") (pintype "passive"))
      (node (ref "R15") (pin "2") (pinfunction "2_2") (pintype "passive"))
      (node (ref "U5") (pin "1") (pinfunction "IN_1") (pintype "passive"))
      (node (ref "U5") (pin "3") (pinfunction "EN_3") (pintype "passive"))
      (node (ref "U6") (pin "5") (pinfunction "CTL_5") (pintype "passive"))
      (node (ref "U6") (pin "8") (pinfunction "VCC_8") (pintype "passive"))
    )
    (net (code "11") (name "/LM12V") (class "Default")
      (node (ref "D8") (pin "1") (pinfunction "C_1") (pintype "passive"))
      (node (ref "R13") (pin "1") (pinfunction "1_1") (pintype "passive"))
      (node (ref "U4") (pin "8") (pinfunction "INPUT_8") (pintype "passive"))
      (node (ref "U7") (pin "1") (pinfunction "Vin_1") (pintype "passive"))
      (node (ref "U8") (pin "1") (pinfunction "Vin_1") (pintype "passive"))
    )
    (net (code "12") (name "/MCLR") (class "Default")
      (node (ref "C5") (pin "1") (pinfunction "1_1") (pintype "passive"))
      (node (ref "J1") (pin "1") (pinfunction "1_1") (pintype "passive"))
      (node (ref "R9") (pin "1") (pinfunction "1_1") (pintype "passive"))
      (node (ref "U3") (pin "7") (pinfunction "~{MCLR}_7") (pintype "passive"))
    )
    (net (code "13") (name "/MCU5.0V") (class "Default")
      (node (ref "R10") (pin "2") (pinfunction "2_2") (pintype "passive"))
      (node (ref "U3") (pin "34") (pinfunction "VBUS_34") (pintype "passive"))
    )
    (net (code "14") (name "/MCU_REF_CLK_1") (class "Default")
      (node (ref "R7") (pin "1") (pinfunction "1_1") (pintype "passive"))
      (node (ref "U3") (pin "52") (pinfunction "PMWR/RP68/RD4_52") (pintype "passive"))
      (node (ref "U3") (pin "53") (pinfunction "PMRD/RP69/RD5_53") (pintype "passive"))
      (node (ref "U3") (pin "54") (pinfunction "C3IN2-/RP70/RD6_54") (pintype "passive"))
      (node (ref "U3") (pin "55") (pinfunction "C3IN1+/VCMPST3/RP71/RD7_55") (pintype "passive"))
    )
    (net (code "15") (name "/MCU_REF_CLK_2") (class "Default")
      (node (ref "R18") (pin "1") (pinfunction "1_1") (pintype "passive"))
      (node (ref "U3") (pin "46") (pinfunction "INT0/DMH/RP64/RD0_46") (pintype "passive"))
      (node (ref "U3") (pin "49") (pinfunction "VCPCON/RP65/RD1_49") (pintype "passive"))
      (node (ref "U3") (pin "50") (pinfunction "DPH/RP66/RD2_50") (pintype "passive"))
      (node (ref "U3") (pin "51") (pinfunction "PMBE/RP67/RD3_51") (pintype "passive"))
    )
    (net (code "16") (name "/MEAS12") (class "Default")
      (node (ref "C1") (pin "1") (pinfunction "1_1") (pintype "passive"))
      (node (ref "R4") (pin "2") (pinfunction "2_2") (pintype "passive"))
      (node (ref "R5") (pin "2") (pinfunction "2_2") (pintype "passive"))
      (node (ref "U3") (pin "18") (pinfunction "PGED1/AN7/RCV/RPI39/RB7_18") (pintype "passive"))
    )
    (net (code "17") (name "/Main OSC In") (class "Default")
      (node (ref "C10") (pin "1") (pinfunction "1_1") (pintype "passive"))
      (node (ref "U3") (pin "39") (pinfunction "OSC1/RPI60/RC12_39") (pintype "passive"))
      (node (ref "Y1") (pin "1") (pinfunction "1_1") (pintype "passive"))
    )
    (net (code "18") (name "/Main OSC Out") (class "Default")
      (node (ref "C11") (pin "1") (pinfunction "1_1") (pintype "passive"))
      (node (ref "U3") (pin "40") (pinfunction "OSC2/CLKO/RC15_40") (pintype "passive"))
      (node (ref "Y1") (pin "2") (pinfunction "2_2") (pintype "passive"))
    )
    (net (code "19") (name "/ORANGE") (class "Default")
      (node (ref "D4") (pin "2") (pinfunction "A_2") (pintype "passive"))
      (node (ref "U3") (pin "45") (pinfunction "PMCS1/RPI75/RD11_45") (pintype "passive"))
    )
    (net (code "20") (name "/PGC") (class "Default")
      (node (ref "J1") (pin "5") (pinfunction "5_5") (pintype "passive"))
      (node (ref "U3") (pin "15") (pinfunction "PGEC3/AN1/VREF-/RPI33/RB1_15") (pintype "passive"))
    )
    (net (code "21") (name "/PGD") (class "Default")
      (node (ref "J1") (pin "4") (pinfunction "4_4") (pintype "passive"))
      (node (ref "U3") (pin "16") (pinfunction "PGED3/AN0/VREF+/RPI32/RB0_16") (pintype "passive"))
    )
    (net (code "22") (name "/PLL_CFG_CLK") (class "Default")
      (node (ref "R26") (pin "1") (pinfunction "1_1") (pintype "passive"))
      (node (ref "U3") (pin "59") (pinfunction "VCMPST2/RP97/RF1_59") (pintype "passive"))
    )
    (net (code "23") (name "/PLL_CFG_DAT") (class "Default")
      (node (ref "U3") (pin "58") (pinfunction "VCMPST1/RP96/RF0_58") (pintype "passive"))
    )
    (net (code "24") (name "/PLL_REF_CLK_1") (class "Default")
      (node (ref "R7") (pin "2") (pinfunction "2_2") (pintype "passive"))
      (node (ref "R8") (pin "2") (pinfunction "2_2") (pintype "passive"))
    )
    (net (code "25") (name "/PLL_REF_CLK_2") (class "Default")
      (node (ref "R18") (pin "2") (pinfunction "2_2") (pintype "passive"))
      (node (ref "R8") (pin "1") (pinfunction "1_1") (pintype "passive"))
    )
    (net (code "26") (name "/PLL_SUP") (class "Default")
      (node (ref "C16") (pin "1") (pinfunction "1_1") (pintype "passive"))
      (node (ref "C17") (pin "1") (pinfunction "1_1") (pintype "passive"))
      (node (ref "FB5") (pin "1") (pinfunction "1_1") (pintype "passive"))
      (node (ref "R16") (pin "1") (pinfunction "1_1") (pintype "passive"))
      (node (ref "U9") (pin "1") (pinfunction "OUT_1") (pintype "passive"))
    )
    (net (code "27") (name "/PWM1H") (class "Default")
      (node (ref "U3") (pin "61") (pinfunction "AN25/PWM1H/PMD1/RPI81/RE1_61") (pintype "passive"))
    )
    (net (code "28") (name "/PWM1L") (class "Default")
      (node (ref "U3") (pin "60") (pinfunction "AN24/PWM1L/PMD0/RP80/RE0_60") (pintype "passive"))
    )
    (net (code "29") (name "/PWM2H") (class "Default")
      (node (ref "U3") (pin "63") (pinfunction "AN27/PWM2H/PMD3/RPI83/RE3_63") (pintype "passive"))
    )
    (net (code "30") (name "/PWM2L") (class "Default")
      (node (ref "U3") (pin "62") (pinfunction "AN26/PWM2L/PMD2/RP82/RE2_62") (pintype "passive"))
    )
    (net (code "31") (name "/PWM3H") (class "Default")
      (node (ref "U3") (pin "1") (pinfunction "AN29/PWM3H/PMD5/RP85/RE5_1") (pintype "passive"))
    )
    (net (code "32") (name "/PWM3L") (class "Default")
      (node (ref "U3") (pin "64") (pinfunction "AN28/PWM3L/PMD4/RP84/RE4_64") (pintype "passive"))
    )
    (net (code "33") (name "/PWM4H") (class "Default")
      (node (ref "U3") (pin "3") (pinfunction "AN31/PWM4H/PMD7/RP87/RE7_3") (pintype "passive"))
    )
    (net (code "34") (name "/PWM4L") (class "Default")
      (node (ref "U3") (pin "2") (pinfunction "AN30/PWM4L/PMD6/RPI86/RE6_2") (pintype "passive"))
    )
    (net (code "35") (name "/RED") (class "Default")
      (node (ref "D1") (pin "2") (pinfunction "A_2") (pintype "passive"))
      (node (ref "U3") (pin "48") (pinfunction "PGEC2/SOSCO/C3IN1-/T1CK/RPI62/RC14_48") (pintype "passive"))
    )
    (net (code "36") (name "/RESET_COLD_L") (class "Default")
      (node (ref "R21") (pin "2") (pinfunction "2_2") (pintype "passive"))
      (node (ref "U3") (pin "8") (pinfunction "C2IN1-/PMA2/RPI121/RG9_8") (pintype "passive"))
    )
    (net (code "37") (name "/SPI_RXD") (class "Default")
      (node (ref "U3") (pin "6") (pinfunction "C2IN3-/SDO2/PMA3/RP120/RG8_6") (pintype "passive"))
    )
    (net (code "38") (name "/SPI_SCLK_IN") (class "Default")
      (node (ref "U3") (pin "4") (pinfunction "C1IN3-/SCK2/PMA5/RP118/RG6_4") (pintype "passive"))
    )
    (net (code "39") (name "/SPI_SS_IN_L_1") (class "Default")
      (node (ref "U3") (pin "32") (pinfunction "SCL2/PMA8/RP101/RF5_32") (pintype "passive"))
    )
    (net (code "40") (name "/SPI_SS_IN_L_2") (class "Default")
      (node (ref "U3") (pin "31") (pinfunction "SDA2/PMA9/RP100/RF4_31") (pintype "passive"))
    )
    (net (code "41") (name "/SPI_SS_IN_L_3") (class "Default")
      (node (ref "U3") (pin "30") (pinfunction "AN15/PMA0/RPI47/RB15_30") (pintype "passive"))
    )
    (net (code "42") (name "/SPI_SS_IN_L_4") (class "Default")
      (node (ref "U3") (pin "29") (pinfunction "AN14/PMA1/RPI46/RB14_29") (pintype "passive"))
    )
    (net (code "43") (name "/SPI_SS_IN_L_5") (class "Default")
      (node (ref "U3") (pin "28") (pinfunction "TDI/AN13/PMA10/RPI45/RB13_28") (pintype "passive"))
    )
    (net (code "44") (name "/SPI_SS_IN_L_6") (class "Default")
      (node (ref "U3") (pin "27") (pinfunction "TCK/AN12/PMA11/RPI44/RB12_27") (pintype "passive"))
    )
    (net (code "45") (name "/SPI_SS_IN_L_7") (class "Default")
      (node (ref "U3") (pin "24") (pinfunction "TDO/AN11/PMA12/RPI43/RB11_24") (pintype "passive"))
    )
    (net (code "46") (name "/SPI_SS_IN_L_8") (class "Default")
      (node (ref "U3") (pin "23") (pinfunction "TMS/AN10/CVREF/PMA13/RPI42/RB10_23") (pintype "passive"))
    )
    (net (code "47") (name "/SPI_TXD") (class "Default")
      (node (ref "U3") (pin "5") (pinfunction "C1IN1-/SDI2/PMA4/RPI119/RG7_5") (pintype "passive"))
    )
    (net (code "48") (name "/USB5.0V") (class "Default")
      (node (ref "D6") (pin "4") (pinfunction "4_4") (pintype "passive"))
      (node (ref "D6") (pin "6") (pinfunction "6_6") (pintype "passive"))
      (node (ref "J2") (pin "1") (pinfunction "1_1") (pintype "passive"))
      (node (ref "R10") (pin "1") (pinfunction "1_1") (pintype "passive"))
      (node (ref "R11") (pin "2") (pinfunction "2_2") (pintype "passive"))
    )
    (net (code "49") (name "/VCAP") (class "Default")
      (node (ref "C2") (pin "1") (pinfunction "1_1") (pintype "passive"))
      (node (ref "U3") (pin "56") (pinfunction "VCAP_56") (pintype "passive"))
    )
    (net (code "50") (name "/VDD_PLL") (class "Default")
      (node (ref "C18") (pin "1") (pinfunction "1_1") (pintype "passive"))
      (node (ref "FB5") (pin "2") (pinfunction "2_2") (pintype "passive"))
      (node (ref "TP2") (pin "1") (pinfunction "1_1") (pintype "passive"))
    )
    (net (code "51") (name "/YELLOW") (class "Default")
      (node (ref "D3") (pin "2") (pinfunction "A_2") (pintype "passive"))
      (node (ref "U3") (pin "44") (pinfunction "ASCL1/PMCS2/RPI74/RD10_44") (pintype "passive"))
    )
    (net (code "52") (name "GND") (class "Default")
      (node (ref "C1") (pin "2") (pinfunction "2_2") (pintype "passive"))
      (node (ref "C10") (pin "2") (pinfunction "2_2") (pintype "passive"))
      (node (ref "C11") (pin "2") (pinfunction "2_2") (pintype "passive"))
      (node (ref "C12") (pin "2") (pinfunction "2_2") (pintype "passive"))
      (node (ref "C13") (pin "1") (pinfunction "1_1") (pintype "passive"))
      (node (ref "C14") (pin "2") (pinfunction "2_2") (pintype "passive"))
      (node (ref "C15") (pin "2") (pinfunction "2_2") (pintype "passive"))
      (node (ref "C16") (pin "2") (pinfunction "2_2") (pintype "passive"))
      (node (ref "C17") (pin "2") (pinfunction "2_2") (pintype "passive"))
      (node (ref "C18") (pin "2") (pinfunction "2_2") (pintype "passive"))
      (node (ref "C2") (pin "2") (pinfunction "2_2") (pintype "passive"))
      (node (ref "C3") (pin "2") (pinfunction "2_2") (pintype "passive"))
      (node (ref "C347") (pin "2") (pinfunction "2_2") (pintype "passive"))
      (node (ref "C4") (pin "2") (pinfunction "2_2") (pintype "passive"))
      (node (ref "C5") (pin "2") (pinfunction "2_2") (pintype "passive"))
      (node (ref "C6") (pin "2") (pinfunction "2_2") (pintype "passive"))
      (node (ref "C7") (pin "2") (pinfunction "2_2") (pintype "passive"))
      (node (ref "C8") (pin "2") (pinfunction "2_2") (pintype "passive"))
      (node (ref "C9") (pin "2") (pinfunction "2_2") (pintype "passive"))
      (node (ref "D1") (pin "1") (pinfunction "C_1") (pintype "passive"))
      (node (ref "D2") (pin "1") (pinfunction "C_1") (pintype "passive"))
      (node (ref "D3") (pin "1") (pinfunction "C_1") (pintype "passive"))
      (node (ref "D4") (pin "1") (pinfunction "C_1") (pintype "passive"))
      (node (ref "D6") (pin "2") (pinfunction "2_2") (pintype "passive"))
      (node (ref "D6") (pin "5") (pinfunction "5_5") (pintype "passive"))
      (node (ref "D9") (pin "2") (pinfunction "A_2") (pintype "passive"))
      (node (ref "J1") (pin "3") (pinfunction "3_3") (pintype "passive"))
      (node (ref "J10") (pin "4") (pinfunction "4_4") (pintype "passive"))
      (node (ref "J10") (pin "5") (pinfunction "5_5") (pintype "passive"))
      (node (ref "J10") (pin "6") (pinfunction "6_6") (pintype "passive"))
      (node (ref "J11") (pin "4") (pinfunction "4_4") (pintype "passive"))
      (node (ref "J11") (pin "5") (pinfunction "5_5") (pintype "passive"))
      (node (ref "J11") (pin "6") (pinfunction "6_6") (pintype "passive"))
      (node (ref "J12") (pin "4") (pinfunction "4_4") (pintype "passive"))
      (node (ref "J12") (pin "5") (pinfunction "5_5") (pintype "passive"))
      (node (ref "J12") (pin "6") (pinfunction "6_6") (pintype "passive"))
      (node (ref "J2") (pin "5") (pinfunction "5_5") (pintype "passive"))
      (node (ref "J2") (pin "6") (pinfunction "6_6") (pintype "passive"))
      (node (ref "J2") (pin "7") (pinfunction "7_7") (pintype "passive"))
      (node (ref "J2") (pin "8") (pinfunction "8_8") (pintype "passive"))
      (node (ref "J2") (pin "9") (pinfunction "9_9") (pintype "passive"))
      (node (ref "J3") (pin "2") (pinfunction "2_2") (pintype "passive"))
      (node (ref "J4") (pin "4") (pinfunction "4_4") (pintype "passive"))
      (node (ref "J4") (pin "5") (pinfunction "5_5") (pintype "passive"))
      (node (ref "J4") (pin "6") (pinfunction "6_6") (pintype "passive"))
      (node (ref "J5") (pin "4") (pinfunction "4_4") (pintype "passive"))
      (node (ref "J5") (pin "5") (pinfunction "5_5") (pintype "passive"))
      (node (ref "J5") (pin "6") (pinfunction "6_6") (pintype "passive"))
      (node (ref "J6") (pin "4") (pinfunction "4_4") (pintype "passive"))
      (node (ref "J6") (pin "5") (pinfunction "5_5") (pintype "passive"))
      (node (ref "J6") (pin "6") (pinfunction "6_6") (pintype "passive"))
      (node (ref "J7") (pin "4") (pinfunction "4_4") (pintype "passive"))
      (node (ref "J7") (pin "5") (pinfunction "5_5") (pintype "passive"))
      (node (ref "J7") (pin "6") (pinfunction "6_6") (pintype "passive"))
      (node (ref "J8") (pin "4") (pinfunction "4_4") (pintype "passive"))
      (node (ref "J8") (pin "5") (pinfunction "5_5") (pintype "passive"))
      (node (ref "J8") (pin "6") (pinfunction "6_6") (pintype "passive"))
      (node (ref "J9") (pin "4") (pinfunction "4_4") (pintype "passive"))
      (node (ref "J9") (pin "5") (pinfunction "5_5") (pintype "passive"))
      (node (ref "J9") (pin "6") (pinfunction "6_6") (pintype "passive"))
      (node (ref "R17") (pin "2") (pinfunction "2_2") (pintype "passive"))
      (node (ref "R26") (pin "2") (pinfunction "2_2") (pintype "passive"))
      (node (ref "R5") (pin "1") (pinfunction "1_1") (pintype "passive"))
      (node (ref "U3") (pin "20") (pinfunction "AVSS_20") (pintype "passive"))
      (node (ref "U3") (pin "25") (pinfunction "VSS_25") (pintype "passive"))
      (node (ref "U3") (pin "41") (pinfunction "VSS_41") (pintype "passive"))
      (node (ref "U3") (pin "9") (pinfunction "VSS_9") (pintype "passive"))
      (node (ref "U4") (pin "2") (pinfunction "GND_2") (pintype "passive"))
      (node (ref "U4") (pin "3") (pinfunction "GND_3") (pintype "passive"))
      (node (ref "U4") (pin "4") (pinfunction "N.C._4") (pintype "passive"))
      (node (ref "U4") (pin "5") (pinfunction "N.C._5") (pintype "passive"))
      (node (ref "U4") (pin "6") (pinfunction "GND_6") (pintype "passive"))
      (node (ref "U4") (pin "7") (pinfunction "GND_7") (pintype "passive"))
      (node (ref "U5") (pin "2") (pinfunction "GND_2") (pintype "passive"))
      (node (ref "U6") (pin "6") (pinfunction "GND_6") (pintype "passive"))
      (node (ref "U6") (pin "7") (pinfunction "GND_7") (pintype "passive"))
      (node (ref "U7") (pin "4") (pinfunction "GND_4") (pintype "passive"))
      (node (ref "U8") (pin "4") (pinfunction "GND_4") (pintype "passive"))
      (node (ref "U9") (pin "6") (pinfunction "GND_6") (pintype "passive"))
      (node (ref "U9") (pin "7") (pinfunction "GND_7") (pintype "passive"))
    )
    (net (code "53") (name "Net-(U3-AN2{slash}C2IN2-{slash}VMIO{slash}RPI34{slash}RB2)") (class "Default")
      (node (ref "TP7") (pin "1") (pinfunction "1_1") (pintype "passive"))
      (node (ref "U3") (pin "14") (pinfunction "AN2/C2IN2-/VMIO/RPI34/RB2_14") (pintype "passive"))
    )
    (net (code "54") (name "Net-(U3-AN3{slash}C2IN1+{slash}VPIO{slash}RPI35{slash}RB3)") (class "Default")
      (node (ref "TP6") (pin "1") (pinfunction "1_1") (pintype "passive"))
      (node (ref "U3") (pin "13") (pinfunction "AN3/C2IN1+/VPIO/RPI35/RB3_13") (pintype "passive"))
    )
    (net (code "55") (name "Net-(U3-AN4{slash}C1IN2-{slash}USBOEN{slash}RPI36{slash}RB4)") (class "Default")
      (node (ref "TP5") (pin "1") (pinfunction "1_1") (pintype "passive"))
      (node (ref "U3") (pin "12") (pinfunction "AN4/C1IN2-/USBOEN/RPI36/RB4_12") (pintype "passive"))
    )
    (net (code "56") (name "Net-(U3-AN5{slash}C1IN1+{slash}VBUSON{slash}VBUSST{slash}RPI37{slash}RB5)") (class "Default")
      (node (ref "TP3") (pin "1") (pinfunction "1_1") (pintype "passive"))
      (node (ref "U3") (pin "11") (pinfunction "AN5/C1IN1+/VBUSON/VBUSST/RPI37/RB5_11") (pintype "passive"))
    )
    (net (code "57") (name "Net-(U3-AN8{slash}PMA6{slash}RPI40{slash}RB8)") (class "Default")
      (node (ref "TP10") (pin "1") (pinfunction "1_1") (pintype "passive"))
      (node (ref "U3") (pin "21") (pinfunction "AN8/PMA6/RPI40/RB8_21") (pintype "passive"))
    )
    (net (code "58") (name "Net-(U3-AN9{slash}PMA7{slash}{slash}RPI41{slash}RB9)") (class "Default")
      (node (ref "TP11") (pin "1") (pinfunction "1_1") (pintype "passive"))
      (node (ref "U3") (pin "22") (pinfunction "AN9/PMA7//RPI41/RB9_22") (pintype "passive"))
    )
    (net (code "59") (name "Net-(U3-ASDA1{slash}DPLN{slash}RPI73{slash}RD9)") (class "Default")
      (node (ref "TP12") (pin "1") (pinfunction "1_1") (pintype "passive"))
      (node (ref "U3") (pin "43") (pinfunction "ASDA1/DPLN/RPI73/RD9_43") (pintype "passive"))
    )
    (net (code "60") (name "Net-(U3-RTCC{slash}DMLN{slash}RPI72{slash}RD8)") (class "Default")
      (node (ref "TP13") (pin "1") (pinfunction "1_1") (pintype "passive"))
      (node (ref "U3") (pin "42") (pinfunction "RTCC/DMLN/RPI72/RD8_42") (pintype "passive"))
    )
    (net (code "61") (name "Net-(U3-USBID{slash}RP99{slash}RF3)") (class "Default")
      (node (ref "TP21") (pin "1") (pinfunction "1_1") (pintype "passive"))
      (node (ref "U3") (pin "33") (pinfunction "USBID/RP99/RF3_33") (pintype "passive"))
    )
    (net (code "62") (name "Net-(U9-ADJ)") (class "Default")
      (node (ref "R16") (pin "2") (pinfunction "2_2") (pintype "passive"))
      (node (ref "R17") (pin "1") (pinfunction "1_1") (pintype "passive"))
      (node (ref "U9") (pin "2") (pinfunction "ADJ_2") (pintype "passive"))
    )
    (net (code "63") (name "unconnected-(J2-Pad4)") (class "Default")
      (node (ref "J2") (pin "4") (pinfunction "4_4") (pintype "passive+no_connect"))
    )
    (net (code "64") (name "unconnected-(U5-N.C.-Pad4)") (class "Default")
      (node (ref "U5") (pin "4") (pinfunction "N.C._4") (pintype "passive+no_connect"))
    )
    (net (code "65") (name "unconnected-(U6-NC-Pad2)") (class "Default")
      (node (ref "U6") (pin "2") (pinfunction "NC_2") (pintype "passive+no_connect"))
    )
    (net (code "66") (name "unconnected-(U6-NC-Pad3)") (class "Default")
      (node (ref "U6") (pin "3") (pinfunction "NC_3") (pintype "passive+no_connect"))
    )
    (net (code "67") (name "unconnected-(U6-NC-Pad4)") (class "Default")
      (node (ref "U6") (pin "4") (pinfunction "NC_4") (pintype "passive+no_connect"))
    )
    (net (code "68") (name "unconnected-(U9-NC-Pad3)") (class "Default")
      (node (ref "U9") (pin "3") (pinfunction "NC_3") (pintype "passive+no_connect"))
    )
    (net (code "69") (name "unconnected-(U9-NC-Pad4)") (class "Default")
      (node (ref "U9") (pin "4") (pinfunction "NC_4") (pintype "passive+no_connect"))
    )
  )
)
